# Flag_Register.net
KiCad netlist of a schematic drawn in EAGLE
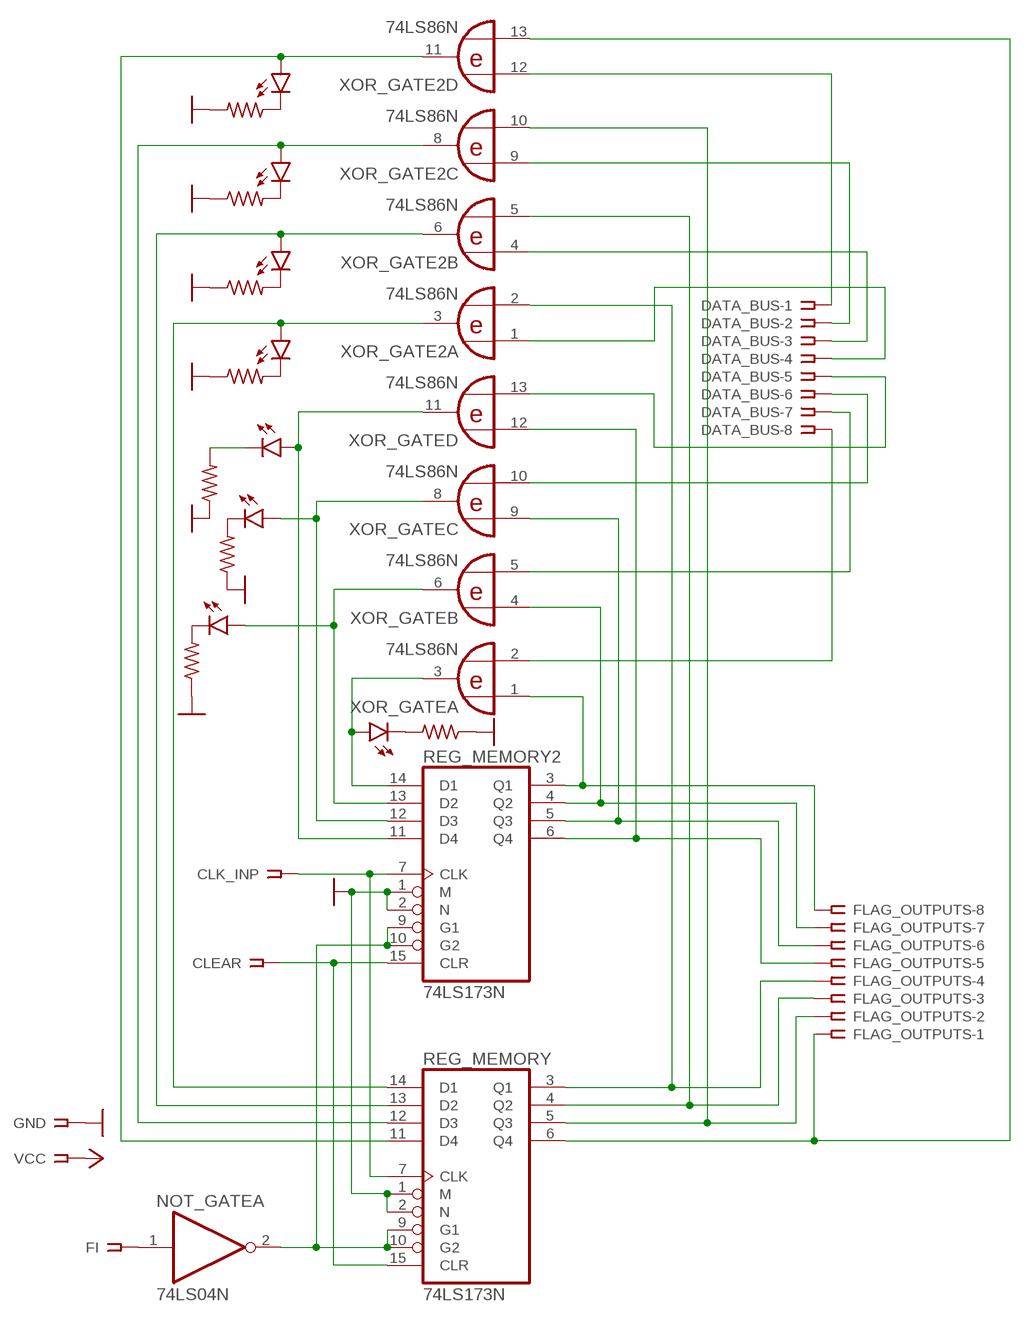
[diagram p0: schematic, sheet 1]

(export (version "E")
  (design (tool "Eeschema 10.0.6"))
  (components
    (comp (ref "CLEAR")
      (value "SSW-101-02-G-S-RA")
      (footprint "eagle-import:SSW-101-02-G-S-RA")
      (fields (field (name "MF") "Samtec Inc."))
      (libsource (lib "eagle-import") (part "SSW-101-02-G-S-RA"))
    )
    (comp (ref "CLK_INP")
      (value "SSW-101-02-G-S-RA")
      (footprint "eagle-import:SSW-101-02-G-S-RA")
      (fields (field (name "MF") "Samtec Inc."))
      (libsource (lib "eagle-import") (part "SSW-101-02-G-S-RA"))
    )
    (comp (ref "DATA_BUS")
      (value "SSW-108-02-G-S")
      (footprint "eagle-import:SSW-108-02-G-S")
      (fields (field (name "MF") "Samtec Inc."))
      (libsource (lib "eagle-import") (part "SSW-108-02-G-S"))
    )
    (comp (ref "FI")
      (value "SSW-101-02-G-S-RA")
      (footprint "eagle-import:SSW-101-02-G-S-RA")
      (fields (field (name "MF") "Samtec Inc."))
      (libsource (lib "eagle-import") (part "SSW-101-02-G-S-RA"))
    )
    (comp (ref "FLAG_OUTPUTS")
      (value "SSW-108-02-G-S")
      (footprint "eagle-import:SSW-108-02-G-S")
      (fields (field (name "MF") "Samtec Inc."))
      (libsource (lib "eagle-import") (part "SSW-108-02-G-S"))
    )
    (comp (ref "GND")
      (value "SSW-101-02-G-S-RA")
      (footprint "eagle-import:SSW-101-02-G-S-RA")
      (fields (field (name "MF") "Samtec Inc."))
      (libsource (lib "eagle-import") (part "SSW-101-02-G-S-RA"))
    )
    (comp (ref "LED1")
      (value "LED5MM")
      (footprint "eagle-import:LED5MM")
      (libsource (lib "eagle-import") (part "LED5MM"))
    )
    (comp (ref "LED2")
      (value "LED5MM")
      (footprint "eagle-import:LED5MM")
      (libsource (lib "eagle-import") (part "LED5MM"))
    )
    (comp (ref "LED3")
      (value "LED5MM")
      (footprint "eagle-import:LED5MM")
      (libsource (lib "eagle-import") (part "LED5MM"))
    )
    (comp (ref "LED4")
      (value "LED5MM")
      (footprint "eagle-import:LED5MM")
      (libsource (lib "eagle-import") (part "LED5MM"))
    )
    (comp (ref "LED5")
      (value "LED5MM")
      (footprint "eagle-import:LED5MM")
      (libsource (lib "eagle-import") (part "LED5MM"))
    )
    (comp (ref "LED6")
      (value "LED5MM")
      (footprint "eagle-import:LED5MM")
      (libsource (lib "eagle-import") (part "LED5MM"))
    )
    (comp (ref "LED7")
      (value "LED5MM")
      (footprint "eagle-import:LED5MM")
      (libsource (lib "eagle-import") (part "LED5MM"))
    )
    (comp (ref "LED8")
      (value "LED5MM")
      (footprint "eagle-import:LED5MM")
      (libsource (lib "eagle-import") (part "LED5MM"))
    )
    (comp (ref "NOT_GATE")
      (value "74LS04N")
      (footprint "eagle-import:DIL14")
      (libsource (lib "eagle-import") (part "7404NLS"))
    )
    (comp (ref "R2")
      (value "220")
      (footprint "eagle-import:0204_7")
      (libsource (lib "eagle-import") (part "R-US_0204/7"))
    )
    (comp (ref "R3")
      (value "220")
      (footprint "eagle-import:0204_7")
      (libsource (lib "eagle-import") (part "R-US_0204/7"))
    )
    (comp (ref "R4")
      (value "220")
      (footprint "eagle-import:0204_7")
      (libsource (lib "eagle-import") (part "R-US_0204/7"))
    )
    (comp (ref "R5")
      (value "220")
      (footprint "eagle-import:0204_7")
      (libsource (lib "eagle-import") (part "R-US_0204/7"))
    )
    (comp (ref "R6")
      (value "220")
      (footprint "eagle-import:0204_7")
      (libsource (lib "eagle-import") (part "R-US_0204/7"))
    )
    (comp (ref "R7")
      (value "220")
      (footprint "eagle-import:0204_7")
      (libsource (lib "eagle-import") (part "R-US_0204/7"))
    )
    (comp (ref "R8")
      (value "220")
      (footprint "eagle-import:0204_7")
      (libsource (lib "eagle-import") (part "R-US_0204/7"))
    )
    (comp (ref "R9")
      (value "220")
      (footprint "eagle-import:0204_7")
      (libsource (lib "eagle-import") (part "R-US_0204/7"))
    )
    (comp (ref "REG_MEMORY")
      (value "74LS173N")
      (footprint "eagle-import:DIL16")
      (libsource (lib "eagle-import") (part "74173NLS"))
    )
    (comp (ref "REG_MEMORY2")
      (value "74LS173N")
      (footprint "eagle-import:DIL16")
      (libsource (lib "eagle-import") (part "74173NLS"))
    )
    (comp (ref "VCC")
      (value "SSW-101-02-G-S-RA")
      (footprint "eagle-import:SSW-101-02-G-S-RA")
      (fields (field (name "MF") "Samtec Inc."))
      (libsource (lib "eagle-import") (part "SSW-101-02-G-S-RA"))
    )
    (comp (ref "XOR_GATE")
      (value "74LS86N")
      (footprint "eagle-import:DIL14")
      (libsource (lib "eagle-import") (part "7486NLS"))
    )
    (comp (ref "XOR_GATE2")
      (value "74LS86N")
      (footprint "eagle-import:DIL14")
      (libsource (lib "eagle-import") (part "7486NLS"))
    )
  )
  (nets
    (net (code "1") (name "GND") (class "Default")
      (node (ref "GND") (pin "1") (pinfunction "1_1") (pintype "passive"))
      (node (ref "R2") (pin "2") (pinfunction "2_2") (pintype "passive"))
      (node (ref "R3") (pin "1") (pinfunction "1_1") (pintype "passive"))
      (node (ref "R4") (pin "1") (pinfunction "1_1") (pintype "passive"))
      (node (ref "R5") (pin "1") (pinfunction "1_1") (pintype "passive"))
      (node (ref "R6") (pin "1") (pinfunction "1_1") (pintype "passive"))
      (node (ref "R7") (pin "1") (pinfunction "1_1") (pintype "passive"))
      (node (ref "R8") (pin "1") (pinfunction "1_1") (pintype "passive"))
      (node (ref "R9") (pin "1") (pinfunction "1_1") (pintype "passive"))
      (node (ref "REG_MEMORY") (pin "1") (pinfunction "M_1") (pintype "input"))
      (node (ref "REG_MEMORY") (pin "2") (pinfunction "N_2") (pintype "input"))
      (node (ref "REG_MEMORY2") (pin "1") (pinfunction "M_1") (pintype "input"))
      (node (ref "REG_MEMORY2") (pin "2") (pinfunction "N_2") (pintype "input"))
    )
    (net (code "2") (name "Net-(DATA_BUSB-1)") (class "Default")
      (node (ref "DATA_BUS") (pin "2") (pinfunction "1_2") (pintype "passive"))
      (node (ref "XOR_GATE2") (pin "9") (pinfunction "I0_9") (pintype "input"))
    )
    (net (code "3") (name "Net-(DATA_BUSC-1)") (class "Default")
      (node (ref "DATA_BUS") (pin "3") (pinfunction "1_3") (pintype "passive"))
      (node (ref "XOR_GATE2") (pin "4") (pinfunction "I0_4") (pintype "input"))
    )
    (net (code "4") (name "Net-(DATA_BUSD-1)") (class "Default")
      (node (ref "DATA_BUS") (pin "4") (pinfunction "1_4") (pintype "passive"))
      (node (ref "XOR_GATE2") (pin "1") (pinfunction "I0_1") (pintype "input"))
    )
    (net (code "5") (name "Net-(DATA_BUSE-1)") (class "Default")
      (node (ref "DATA_BUS") (pin "5") (pinfunction "1_5") (pintype "passive"))
      (node (ref "XOR_GATE") (pin "13") (pinfunction "I1_13") (pintype "input"))
    )
    (net (code "6") (name "Net-(DATA_BUSF-1)") (class "Default")
      (node (ref "DATA_BUS") (pin "6") (pinfunction "1_6") (pintype "passive"))
      (node (ref "XOR_GATE") (pin "10") (pinfunction "I1_10") (pintype "input"))
    )
    (net (code "7") (name "Net-(DATA_BUSG-1)") (class "Default")
      (node (ref "DATA_BUS") (pin "7") (pinfunction "1_7") (pintype "passive"))
      (node (ref "XOR_GATE") (pin "5") (pinfunction "I1_5") (pintype "input"))
    )
    (net (code "8") (name "Net-(DATA_BUSH-1)") (class "Default")
      (node (ref "DATA_BUS") (pin "8") (pinfunction "1_8") (pintype "passive"))
      (node (ref "XOR_GATE") (pin "2") (pinfunction "I1_2") (pintype "input"))
    )
    (net (code "9") (name "Net-(FLAG_OUTPUTSB-1)") (class "Default")
      (node (ref "FLAG_OUTPUTS") (pin "2") (pinfunction "1_2") (pintype "passive"))
      (node (ref "REG_MEMORY") (pin "5") (pinfunction "Q3_5") (pintype "tri_state"))
      (node (ref "XOR_GATE2") (pin "10") (pinfunction "I1_10") (pintype "input"))
    )
    (net (code "10") (name "Net-(FLAG_OUTPUTSC-1)") (class "Default")
      (node (ref "FLAG_OUTPUTS") (pin "3") (pinfunction "1_3") (pintype "passive"))
      (node (ref "REG_MEMORY") (pin "4") (pinfunction "Q2_4") (pintype "tri_state"))
      (node (ref "XOR_GATE2") (pin "5") (pinfunction "I1_5") (pintype "input"))
    )
    (net (code "11") (name "Net-(FLAG_OUTPUTSD-1)") (class "Default")
      (node (ref "FLAG_OUTPUTS") (pin "4") (pinfunction "1_4") (pintype "passive"))
      (node (ref "REG_MEMORY") (pin "3") (pinfunction "Q1_3") (pintype "tri_state"))
      (node (ref "XOR_GATE2") (pin "2") (pinfunction "I1_2") (pintype "input"))
    )
    (net (code "12") (name "Net-(FLAG_OUTPUTSE-1)") (class "Default")
      (node (ref "FLAG_OUTPUTS") (pin "5") (pinfunction "1_5") (pintype "passive"))
      (node (ref "REG_MEMORY2") (pin "6") (pinfunction "Q4_6") (pintype "tri_state"))
      (node (ref "XOR_GATE") (pin "12") (pinfunction "I0_12") (pintype "input"))
    )
    (net (code "13") (name "Net-(FLAG_OUTPUTSF-1)") (class "Default")
      (node (ref "FLAG_OUTPUTS") (pin "6") (pinfunction "1_6") (pintype "passive"))
      (node (ref "REG_MEMORY2") (pin "5") (pinfunction "Q3_5") (pintype "tri_state"))
      (node (ref "XOR_GATE") (pin "9") (pinfunction "I0_9") (pintype "input"))
    )
    (net (code "14") (name "Net-(FLAG_OUTPUTSG-1)") (class "Default")
      (node (ref "FLAG_OUTPUTS") (pin "7") (pinfunction "1_7") (pintype "passive"))
      (node (ref "REG_MEMORY2") (pin "4") (pinfunction "Q2_4") (pintype "tri_state"))
      (node (ref "XOR_GATE") (pin "4") (pinfunction "I0_4") (pintype "input"))
    )
    (net (code "15") (name "Net-(FLAG_OUTPUTSH-1)") (class "Default")
      (node (ref "FLAG_OUTPUTS") (pin "8") (pinfunction "1_8") (pintype "passive"))
      (node (ref "REG_MEMORY2") (pin "3") (pinfunction "Q1_3") (pintype "tri_state"))
      (node (ref "XOR_GATE") (pin "1") (pinfunction "I0_1") (pintype "input"))
    )
    (net (code "16") (name "Net-(LED1-C)") (class "Default")
      (node (ref "LED1") (pin "K") (pinfunction "C_K") (pintype "passive"))
      (node (ref "R2") (pin "1") (pinfunction "1_1") (pintype "passive"))
    )
    (net (code "17") (name "Net-(LED2-C)") (class "Default")
      (node (ref "LED2") (pin "K") (pinfunction "C_K") (pintype "passive"))
      (node (ref "R3") (pin "2") (pinfunction "2_2") (pintype "passive"))
    )
    (net (code "18") (name "Net-(LED3-C)") (class "Default")
      (node (ref "LED3") (pin "K") (pinfunction "C_K") (pintype "passive"))
      (node (ref "R4") (pin "2") (pinfunction "2_2") (pintype "passive"))
    )
    (net (code "19") (name "Net-(LED4-C)") (class "Default")
      (node (ref "LED4") (pin "K") (pinfunction "C_K") (pintype "passive"))
      (node (ref "R5") (pin "2") (pinfunction "2_2") (pintype "passive"))
    )
    (net (code "20") (name "Net-(LED5-C)") (class "Default")
      (node (ref "LED5") (pin "K") (pinfunction "C_K") (pintype "passive"))
      (node (ref "R6") (pin "2") (pinfunction "2_2") (pintype "passive"))
    )
    (net (code "21") (name "Net-(LED6-C)") (class "Default")
      (node (ref "LED6") (pin "K") (pinfunction "C_K") (pintype "passive"))
      (node (ref "R7") (pin "2") (pinfunction "2_2") (pintype "passive"))
    )
    (net (code "22") (name "Net-(LED7-C)") (class "Default")
      (node (ref "LED7") (pin "K") (pinfunction "C_K") (pintype "passive"))
      (node (ref "R8") (pin "2") (pinfunction "2_2") (pintype "passive"))
    )
    (net (code "23") (name "Net-(LED8-C)") (class "Default")
      (node (ref "LED8") (pin "K") (pinfunction "C_K") (pintype "passive"))
      (node (ref "R9") (pin "2") (pinfunction "2_2") (pintype "passive"))
    )
    (net (code "24") (name "Net-(NOT_GATEA-I)") (class "Default")
      (node (ref "FI") (pin "1") (pinfunction "1_1") (pintype "passive"))
      (node (ref "NOT_GATE") (pin "1") (pinfunction "I_1") (pintype "input"))
    )
    (net (code "25") (name "Net-(NOT_GATEA-O)") (class "Default")
      (node (ref "NOT_GATE") (pin "2") (pinfunction "O_2") (pintype "output"))
      (node (ref "REG_MEMORY") (pin "10") (pinfunction "G2_10") (pintype "input"))
      (node (ref "REG_MEMORY") (pin "9") (pinfunction "G1_9") (pintype "input"))
      (node (ref "REG_MEMORY2") (pin "10") (pinfunction "G2_10") (pintype "input"))
      (node (ref "REG_MEMORY2") (pin "9") (pinfunction "G1_9") (pintype "input"))
    )
    (net (code "26") (name "Net-(REG_MEMORY2A-CLK)") (class "Default")
      (node (ref "CLK_INP") (pin "1") (pinfunction "1_1") (pintype "passive"))
      (node (ref "REG_MEMORY") (pin "7") (pinfunction "CLK_7") (pintype "input"))
      (node (ref "REG_MEMORY2") (pin "7") (pinfunction "CLK_7") (pintype "input"))
    )
    (net (code "27") (name "Net-(REG_MEMORY2A-CLR)") (class "Default")
      (node (ref "CLEAR") (pin "1") (pinfunction "1_1") (pintype "passive"))
      (node (ref "REG_MEMORY") (pin "15") (pinfunction "CLR_15") (pintype "input"))
      (node (ref "REG_MEMORY2") (pin "15") (pinfunction "CLR_15") (pintype "input"))
    )
    (net (code "28") (name "Net-(REG_MEMORY2A-D1)") (class "Default")
      (node (ref "LED8") (pin "A") (pinfunction "A_A") (pintype "passive"))
      (node (ref "REG_MEMORY2") (pin "14") (pinfunction "D1_14") (pintype "input"))
      (node (ref "XOR_GATE") (pin "3") (pinfunction "O_3") (pintype "output"))
    )
    (net (code "29") (name "Net-(REG_MEMORY2A-D2)") (class "Default")
      (node (ref "LED7") (pin "A") (pinfunction "A_A") (pintype "passive"))
      (node (ref "REG_MEMORY2") (pin "13") (pinfunction "D2_13") (pintype "input"))
      (node (ref "XOR_GATE") (pin "6") (pinfunction "O_6") (pintype "output"))
    )
    (net (code "30") (name "Net-(REG_MEMORY2A-D3)") (class "Default")
      (node (ref "LED6") (pin "A") (pinfunction "A_A") (pintype "passive"))
      (node (ref "REG_MEMORY2") (pin "12") (pinfunction "D3_12") (pintype "input"))
      (node (ref "XOR_GATE") (pin "8") (pinfunction "O_8") (pintype "output"))
    )
    (net (code "31") (name "Net-(REG_MEMORY2A-D4)") (class "Default")
      (node (ref "LED5") (pin "A") (pinfunction "A_A") (pintype "passive"))
      (node (ref "REG_MEMORY2") (pin "11") (pinfunction "D4_11") (pintype "input"))
      (node (ref "XOR_GATE") (pin "11") (pinfunction "O_11") (pintype "output"))
    )
    (net (code "32") (name "Net-(REG_MEMORYA-D1)") (class "Default")
      (node (ref "LED4") (pin "A") (pinfunction "A_A") (pintype "passive"))
      (node (ref "REG_MEMORY") (pin "14") (pinfunction "D1_14") (pintype "input"))
      (node (ref "XOR_GATE2") (pin "3") (pinfunction "O_3") (pintype "output"))
    )
    (net (code "33") (name "Net-(REG_MEMORYA-D2)") (class "Default")
      (node (ref "LED3") (pin "A") (pinfunction "A_A") (pintype "passive"))
      (node (ref "REG_MEMORY") (pin "13") (pinfunction "D2_13") (pintype "input"))
      (node (ref "XOR_GATE2") (pin "6") (pinfunction "O_6") (pintype "output"))
    )
    (net (code "34") (name "Net-(REG_MEMORYA-D3)") (class "Default")
      (node (ref "LED2") (pin "A") (pinfunction "A_A") (pintype "passive"))
      (node (ref "REG_MEMORY") (pin "12") (pinfunction "D3_12") (pintype "input"))
      (node (ref "XOR_GATE2") (pin "8") (pinfunction "O_8") (pintype "output"))
    )
    (net (code "35") (name "Net-(REG_MEMORYA-D4)") (class "Default")
      (node (ref "LED1") (pin "A") (pinfunction "A_A") (pintype "passive"))
      (node (ref "REG_MEMORY") (pin "11") (pinfunction "D4_11") (pintype "input"))
      (node (ref "XOR_GATE2") (pin "11") (pinfunction "O_11") (pintype "output"))
    )
    (net (code "36") (name "Net-(REG_MEMORYA-Q4)") (class "Default")
      (node (ref "FLAG_OUTPUTS") (pin "1") (pinfunction "1_1") (pintype "passive"))
      (node (ref "REG_MEMORY") (pin "6") (pinfunction "Q4_6") (pintype "tri_state"))
      (node (ref "XOR_GATE2") (pin "13") (pinfunction "I1_13") (pintype "input"))
    )
    (net (code "37") (name "Net-(XOR_GATE2D-I0)") (class "Default")
      (node (ref "DATA_BUS") (pin "1") (pinfunction "1_1") (pintype "passive"))
      (node (ref "XOR_GATE2") (pin "12") (pinfunction "I0_12") (pintype "input"))
    )
    (net (code "38") (name "VCC") (class "Default")
      (node (ref "VCC") (pin "1") (pinfunction "1_1") (pintype "passive"))
    )
  )
)
